# TempDataLogger.net
KiCad netlist of a schematic drawn in EasyEDA
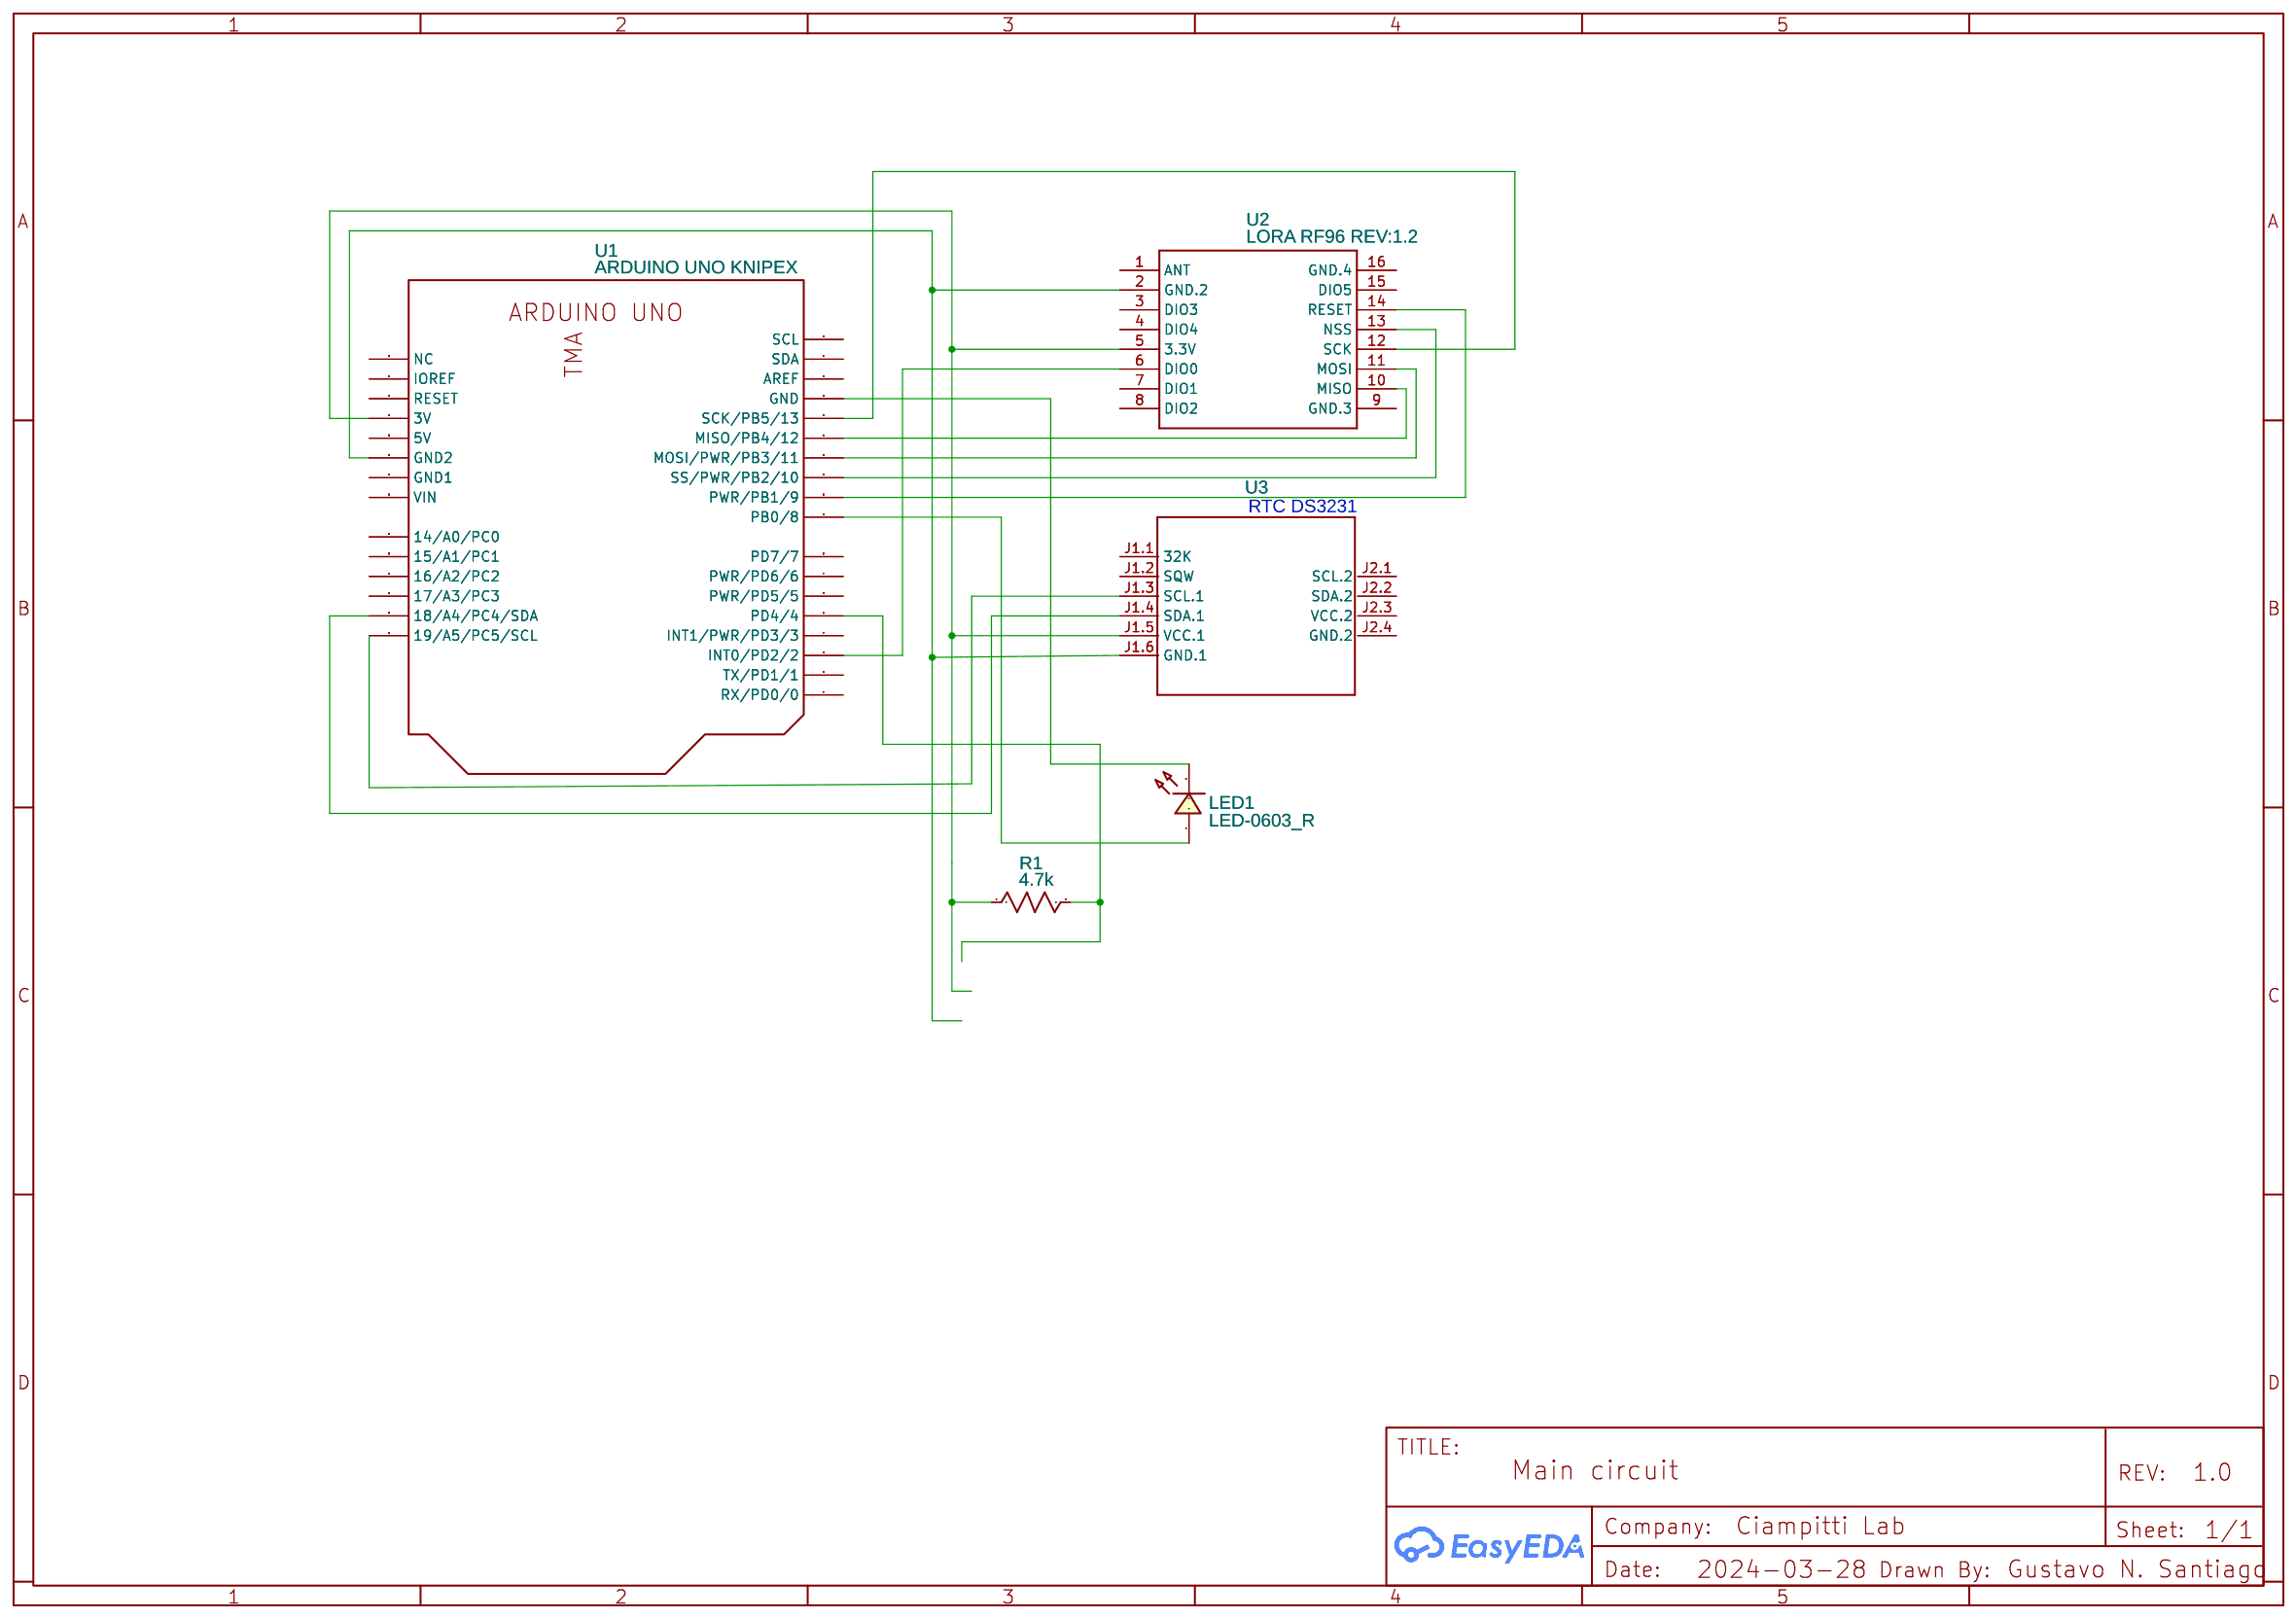
[diagram p0: Main circuit]
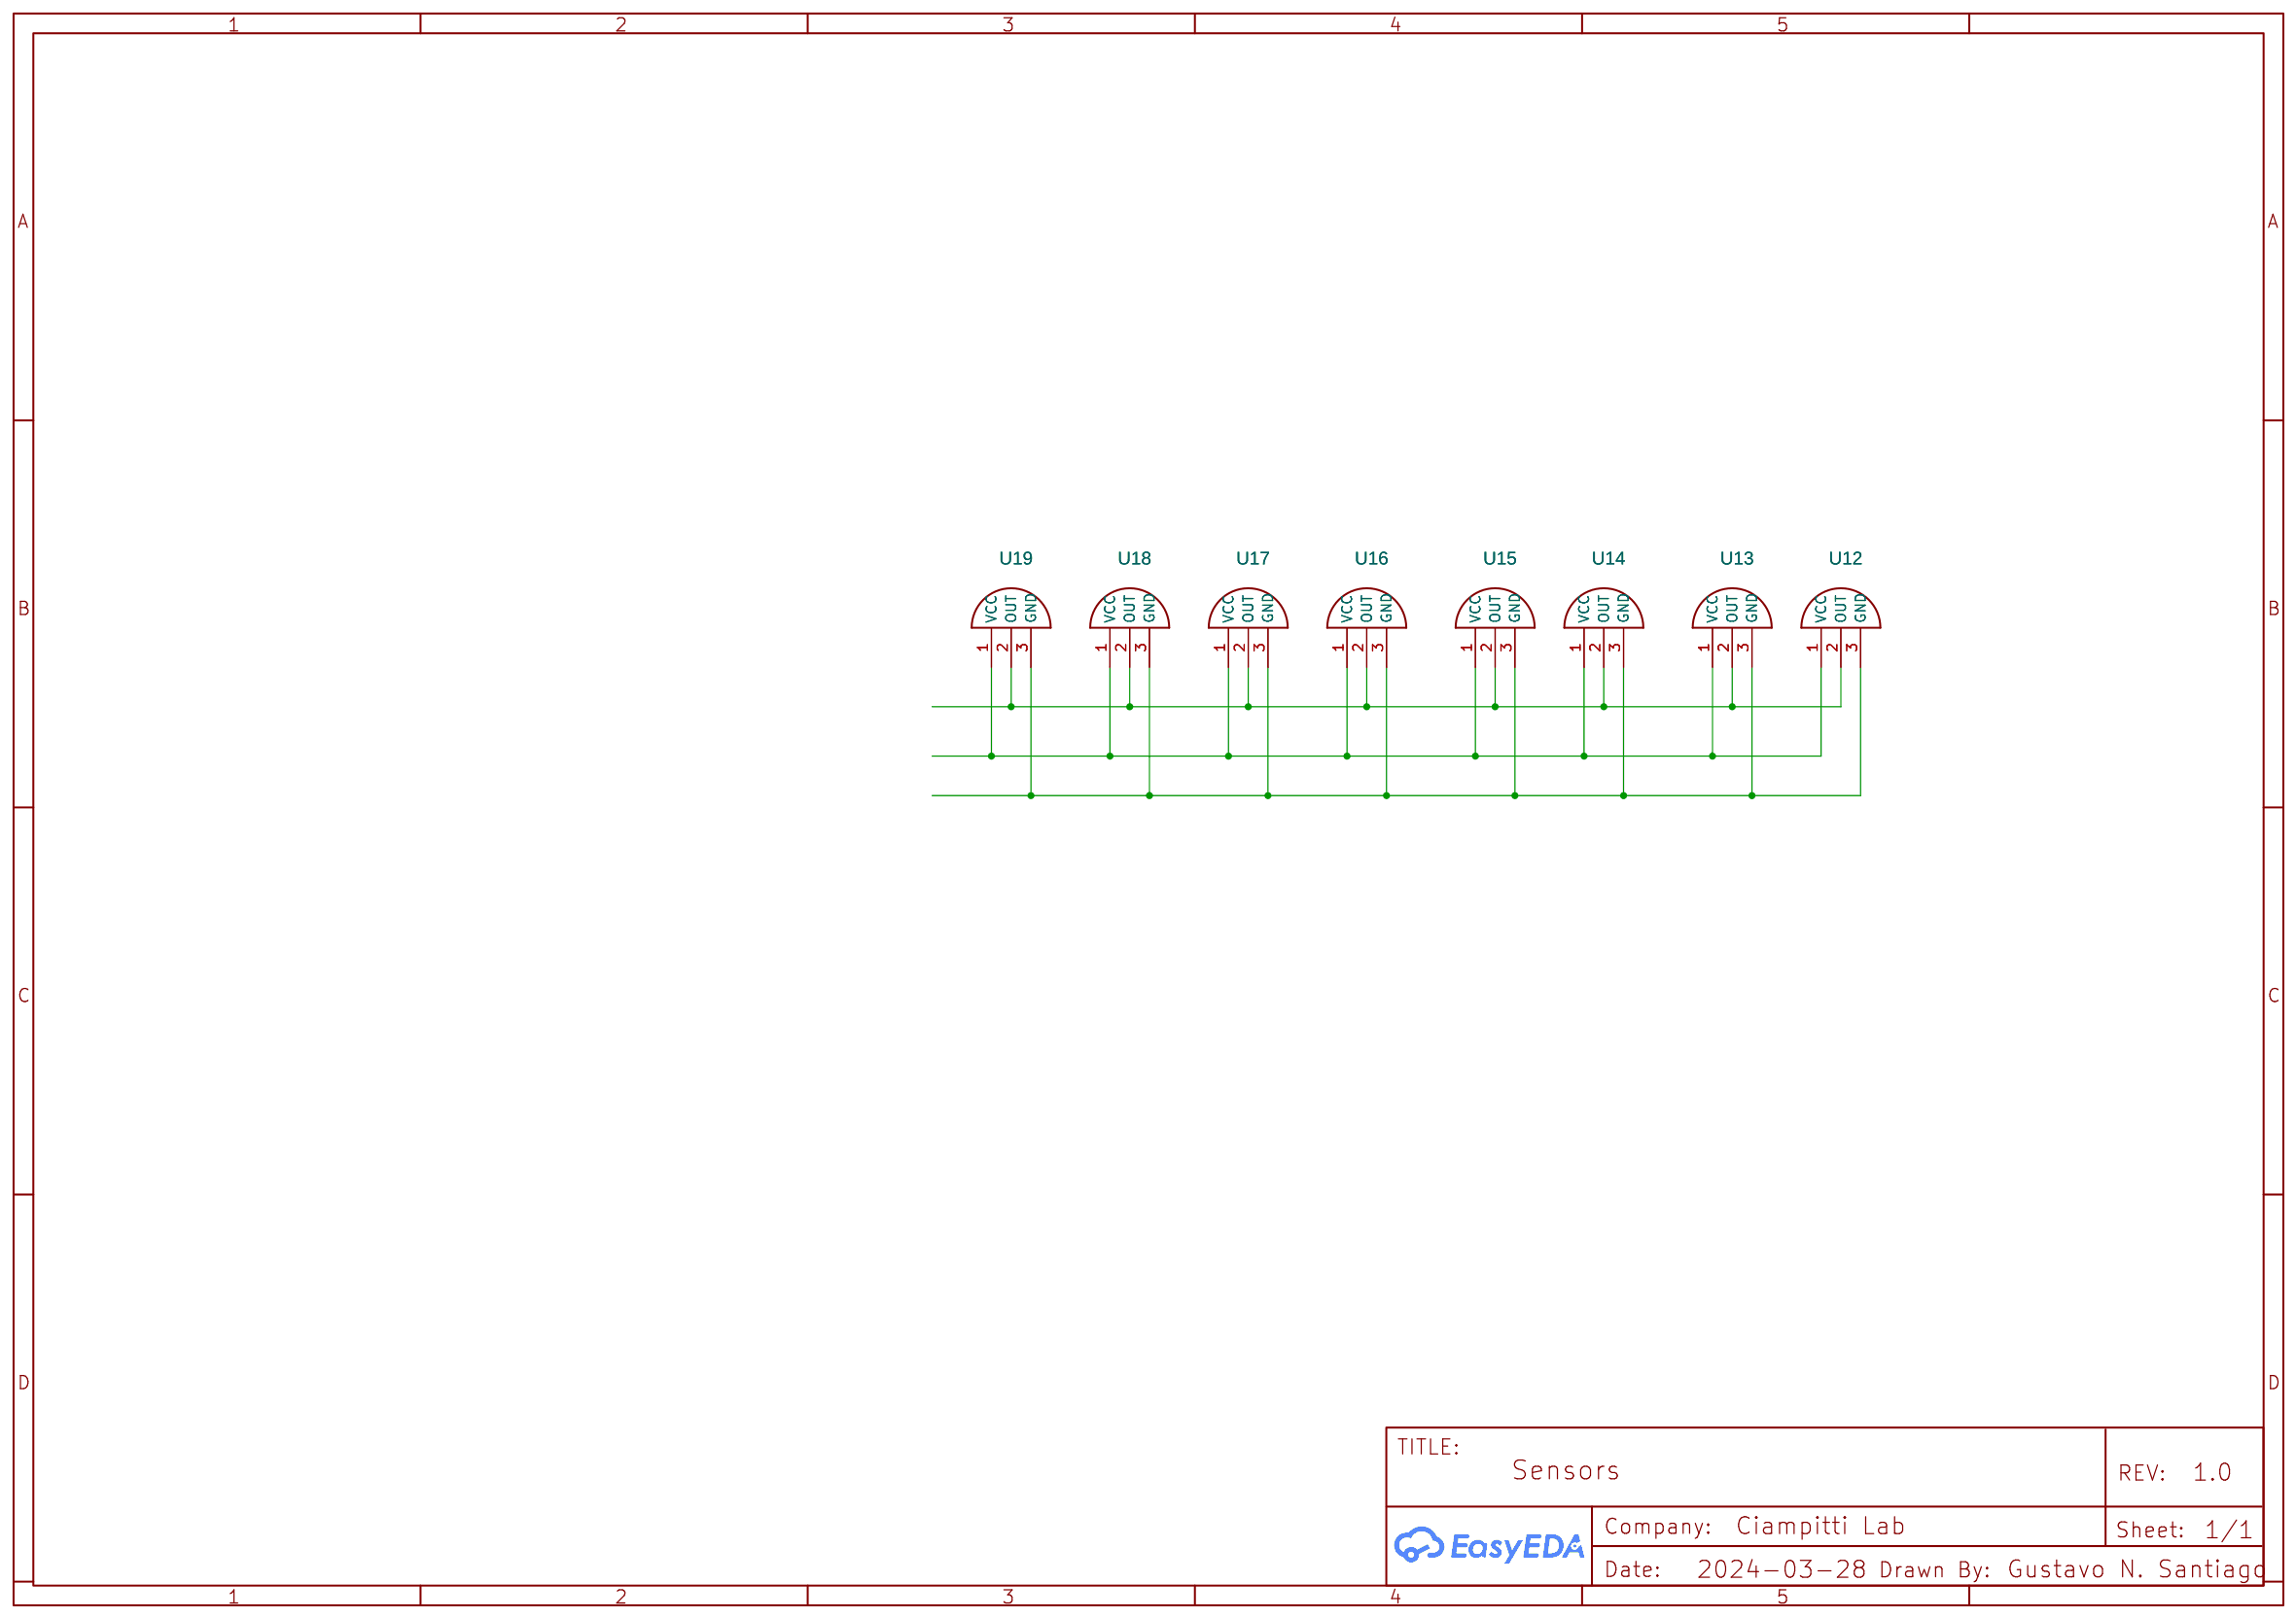
[diagram p1: Sensors]

(export (version "E")
  (design (tool "Eeschema 10.0.6"))
  (components
    (comp (ref "LED1")
      (value "LED-0603_R")
      (fields
        (field (name "Manufacturer Part") "19-217/R6C-AL1M2VY/3T")
        (field (name "Manufacturer") "EVERLIGHT(台湾亿光)")
      )
      (libsource (lib "") (part "LED-0603_R"))
    )
    (comp (ref "R1") (value "4.7k") (libsource (lib "") (part "R_0603_US")))
    (comp (ref "U1") (value "ARDUINO UNO KNIPEX") (libsource (lib "") (part "ARDUINO UNO KNIPEX")))
    (comp (ref "U2") (value "LORA RF96 REV:1.2") (libsource (lib "") (part "LORA RF96 REV{colon}1.2")))
    (comp (ref "U3") (value "NO") (libsource (lib "") (part "RTC-DS3231-AT24C32")))
    (comp (ref "U12")
      (value "NO")
      (fields (field (name "Manufacturer Part") "New SchematicLib"))
      (libsource (lib "") (part "DS18B20 TEMPERATURE"))
    )
    (comp (ref "U13")
      (value "NO")
      (fields (field (name "Manufacturer Part") "New SchematicLib"))
      (libsource (lib "") (part "DS18B20 TEMPERATURE"))
    )
    (comp (ref "U14")
      (value "NO")
      (fields (field (name "Manufacturer Part") "New SchematicLib"))
      (libsource (lib "") (part "DS18B20 TEMPERATURE"))
    )
    (comp (ref "U15")
      (value "NO")
      (fields (field (name "Manufacturer Part") "New SchematicLib"))
      (libsource (lib "") (part "DS18B20 TEMPERATURE"))
    )
    (comp (ref "U16")
      (value "NO")
      (fields (field (name "Manufacturer Part") "New SchematicLib"))
      (libsource (lib "") (part "DS18B20 TEMPERATURE"))
    )
    (comp (ref "U17")
      (value "NO")
      (fields (field (name "Manufacturer Part") "New SchematicLib"))
      (libsource (lib "") (part "DS18B20 TEMPERATURE"))
    )
    (comp (ref "U18")
      (value "NO")
      (fields (field (name "Manufacturer Part") "New SchematicLib"))
      (libsource (lib "") (part "DS18B20 TEMPERATURE"))
    )
    (comp (ref "U19")
      (value "NO")
      (fields (field (name "Manufacturer Part") "New SchematicLib"))
      (libsource (lib "") (part "DS18B20 TEMPERATURE"))
    )
  )
  (nets
    (net (code "1") (name "Net-(U1-3V)") (class "Default")
      (node (ref "R1") (pin "1") (pinfunction "1_1") (pintype "unspecified"))
      (node (ref "U1") (pin "29") (pinfunction "3V_29") (pintype "passive"))
      (node (ref "U2") (pin "5") (pinfunction "3.3V_5") (pintype "passive"))
      (node (ref "U3") (pin "J1.5") (pinfunction "VCC.1_J1.5") (pintype "bidirectional"))
    )
    (net (code "2") (name "Net-(U1-18{slash}A4{slash}PC4{slash}SDA)") (class "Default")
      (node (ref "U1") (pin "20") (pinfunction "18/A4/PC4/SDA_20") (pintype "unspecified"))
      (node (ref "U3") (pin "J1.4") (pinfunction "SDA.1_J1.4") (pintype "bidirectional"))
    )
    (net (code "3") (name "Net-(U1-19{slash}A5{slash}PC5{slash}SCL)") (class "Default")
      (node (ref "U1") (pin "19") (pinfunction "19/A5/PC5/SCL_19") (pintype "unspecified"))
      (node (ref "U3") (pin "J1.3") (pinfunction "SCL.1_J1.3") (pintype "bidirectional"))
    )
    (net (code "4") (name "Net-(U1-GND)") (class "Default")
      (node (ref "LED1") (pin "2") (pinfunction "2_2") (pintype "unspecified"))
      (node (ref "U1") (pin "15") (pinfunction "GND_15") (pintype "passive"))
    )
    (net (code "5") (name "Net-(U1-GND2)") (class "Default")
      (node (ref "U1") (pin "27") (pinfunction "GND2_27") (pintype "passive"))
      (node (ref "U2") (pin "2") (pinfunction "GND.2_2") (pintype "passive"))
      (node (ref "U3") (pin "J1.6") (pinfunction "GND.1_J1.6") (pintype "bidirectional"))
    )
    (net (code "6") (name "Net-(U1-INT0{slash}PD2{slash}2)") (class "Default")
      (node (ref "U1") (pin "3") (pinfunction "INT0/PD2/2_3") (pintype "unspecified"))
      (node (ref "U2") (pin "6") (pinfunction "DIO0_6") (pintype "unspecified"))
    )
    (net (code "7") (name "Net-(U1-MISO{slash}PB4{slash}12)") (class "Default")
      (node (ref "U1") (pin "13") (pinfunction "MISO/PB4/12_13") (pintype "unspecified"))
      (node (ref "U2") (pin "10") (pinfunction "MISO_10") (pintype "unspecified"))
    )
    (net (code "8") (name "Net-(U1-MOSI{slash}PWR{slash}PB3{slash}11)") (class "Default")
      (node (ref "U1") (pin "12") (pinfunction "MOSI/PWR/PB3/11_12") (pintype "unspecified"))
      (node (ref "U2") (pin "11") (pinfunction "MOSI_11") (pintype "unspecified"))
    )
    (net (code "9") (name "Net-(U1-PB0{slash}8)") (class "Default")
      (node (ref "LED1") (pin "1") (pinfunction "1_1") (pintype "unspecified"))
      (node (ref "U1") (pin "9") (pinfunction "PB0/8_9") (pintype "unspecified"))
    )
    (net (code "10") (name "Net-(U1-PD4{slash}4)") (class "Default")
      (node (ref "R1") (pin "2") (pinfunction "2_2") (pintype "unspecified"))
      (node (ref "U1") (pin "5") (pinfunction "PD4/4_5") (pintype "unspecified"))
    )
    (net (code "11") (name "Net-(U1-PWR{slash}PB1{slash}9)") (class "Default")
      (node (ref "U1") (pin "10") (pinfunction "PWR/PB1/9_10") (pintype "unspecified"))
      (node (ref "U2") (pin "14") (pinfunction "RESET_14") (pintype "unspecified"))
    )
    (net (code "12") (name "Net-(U1-SCK{slash}PB5{slash}13)") (class "Default")
      (node (ref "U1") (pin "14") (pinfunction "SCK/PB5/13_14") (pintype "unspecified"))
      (node (ref "U2") (pin "12") (pinfunction "SCK_12") (pintype "unspecified"))
    )
    (net (code "13") (name "Net-(U1-SS{slash}PWR{slash}PB2{slash}10)") (class "Default")
      (node (ref "U1") (pin "11") (pinfunction "SS/PWR/PB2/10_11") (pintype "unspecified"))
      (node (ref "U2") (pin "13") (pinfunction "NSS_13") (pintype "unspecified"))
    )
    (net (code "14") (name "Net-(U12-GND)") (class "Default")
      (node (ref "U12") (pin "3") (pinfunction "GND_3") (pintype "unspecified"))
      (node (ref "U13") (pin "3") (pinfunction "GND_3") (pintype "unspecified"))
      (node (ref "U14") (pin "3") (pinfunction "GND_3") (pintype "unspecified"))
      (node (ref "U15") (pin "3") (pinfunction "GND_3") (pintype "unspecified"))
      (node (ref "U16") (pin "3") (pinfunction "GND_3") (pintype "unspecified"))
      (node (ref "U17") (pin "3") (pinfunction "GND_3") (pintype "unspecified"))
      (node (ref "U18") (pin "3") (pinfunction "GND_3") (pintype "unspecified"))
      (node (ref "U19") (pin "3") (pinfunction "GND_3") (pintype "unspecified"))
    )
    (net (code "15") (name "Net-(U12-OUT)") (class "Default")
      (node (ref "U12") (pin "2") (pinfunction "OUT_2") (pintype "unspecified"))
      (node (ref "U13") (pin "2") (pinfunction "OUT_2") (pintype "unspecified"))
      (node (ref "U14") (pin "2") (pinfunction "OUT_2") (pintype "unspecified"))
      (node (ref "U15") (pin "2") (pinfunction "OUT_2") (pintype "unspecified"))
      (node (ref "U16") (pin "2") (pinfunction "OUT_2") (pintype "unspecified"))
      (node (ref "U17") (pin "2") (pinfunction "OUT_2") (pintype "unspecified"))
      (node (ref "U18") (pin "2") (pinfunction "OUT_2") (pintype "unspecified"))
      (node (ref "U19") (pin "2") (pinfunction "OUT_2") (pintype "unspecified"))
    )
    (net (code "16") (name "Net-(U12-VCC)") (class "Default")
      (node (ref "U12") (pin "1") (pinfunction "VCC_1") (pintype "unspecified"))
      (node (ref "U13") (pin "1") (pinfunction "VCC_1") (pintype "unspecified"))
      (node (ref "U14") (pin "1") (pinfunction "VCC_1") (pintype "unspecified"))
      (node (ref "U15") (pin "1") (pinfunction "VCC_1") (pintype "unspecified"))
      (node (ref "U16") (pin "1") (pinfunction "VCC_1") (pintype "unspecified"))
      (node (ref "U17") (pin "1") (pinfunction "VCC_1") (pintype "unspecified"))
      (node (ref "U18") (pin "1") (pinfunction "VCC_1") (pintype "unspecified"))
      (node (ref "U19") (pin "1") (pinfunction "VCC_1") (pintype "unspecified"))
    )
    (net (code "17") (name "unconnected-(U1-5V-Pad28)") (class "Default")
      (node (ref "U1") (pin "28") (pinfunction "5V_28") (pintype "passive"))
    )
    (net (code "18") (name "unconnected-(U1-14{slash}A0{slash}PC0-Pad24)") (class "Default")
      (node (ref "U1") (pin "24") (pinfunction "14/A0/PC0_24") (pintype "unspecified"))
    )
    (net (code "19") (name "unconnected-(U1-15{slash}A1{slash}PC1-Pad23)") (class "Default")
      (node (ref "U1") (pin "23") (pinfunction "15/A1/PC1_23") (pintype "unspecified"))
    )
    (net (code "20") (name "unconnected-(U1-16{slash}A2{slash}PC2-Pad22)") (class "Default")
      (node (ref "U1") (pin "22") (pinfunction "16/A2/PC2_22") (pintype "unspecified"))
    )
    (net (code "21") (name "unconnected-(U1-17{slash}A3{slash}PC3-Pad21)") (class "Default")
      (node (ref "U1") (pin "21") (pinfunction "17/A3/PC3_21") (pintype "unspecified"))
    )
    (net (code "22") (name "unconnected-(U1-AREF-Pad16)") (class "Default")
      (node (ref "U1") (pin "16") (pinfunction "AREF_16") (pintype "unspecified"))
    )
    (net (code "23") (name "unconnected-(U1-GND1-Pad26)") (class "Default")
      (node (ref "U1") (pin "26") (pinfunction "GND1_26") (pintype "passive"))
    )
    (net (code "24") (name "unconnected-(U1-INT1{slash}PWR{slash}PD3{slash}3-Pad4)") (class "Default")
      (node (ref "U1") (pin "4") (pinfunction "INT1/PWR/PD3/3_4") (pintype "unspecified"))
    )
    (net (code "25") (name "unconnected-(U1-IOREF-Pad31)") (class "Default")
      (node (ref "U1") (pin "31") (pinfunction "IOREF_31") (pintype "unspecified"))
    )
    (net (code "26") (name "unconnected-(U1-NC-Pad32)") (class "Default")
      (node (ref "U1") (pin "32") (pinfunction "NC_32") (pintype "unspecified"))
    )
    (net (code "27") (name "unconnected-(U1-PD7{slash}7-Pad8)") (class "Default")
      (node (ref "U1") (pin "8") (pinfunction "PD7/7_8") (pintype "unspecified"))
    )
    (net (code "28") (name "unconnected-(U1-PWR{slash}PD5{slash}5-Pad6)") (class "Default")
      (node (ref "U1") (pin "6") (pinfunction "PWR/PD5/5_6") (pintype "unspecified"))
    )
    (net (code "29") (name "unconnected-(U1-PWR{slash}PD6{slash}6-Pad7)") (class "Default")
      (node (ref "U1") (pin "7") (pinfunction "PWR/PD6/6_7") (pintype "unspecified"))
    )
    (net (code "30") (name "unconnected-(U1-RESET-Pad30)") (class "Default")
      (node (ref "U1") (pin "30") (pinfunction "RESET_30") (pintype "unspecified"))
    )
    (net (code "31") (name "unconnected-(U1-RX{slash}PD0{slash}0-Pad1)") (class "Default")
      (node (ref "U1") (pin "1") (pinfunction "RX/PD0/0_1") (pintype "unspecified"))
    )
    (net (code "32") (name "unconnected-(U1-SCL-Pad18)") (class "Default")
      (node (ref "U1") (pin "18") (pinfunction "SCL_18") (pintype "unspecified"))
    )
    (net (code "33") (name "unconnected-(U1-SDA-Pad17)") (class "Default")
      (node (ref "U1") (pin "17") (pinfunction "SDA_17") (pintype "unspecified"))
    )
    (net (code "34") (name "unconnected-(U1-TX{slash}PD1{slash}1-Pad2)") (class "Default")
      (node (ref "U1") (pin "2") (pinfunction "TX/PD1/1_2") (pintype "unspecified"))
    )
    (net (code "35") (name "unconnected-(U1-VIN-Pad25)") (class "Default")
      (node (ref "U1") (pin "25") (pinfunction "VIN_25") (pintype "passive"))
    )
    (net (code "36") (name "unconnected-(U2-ANT-Pad1)") (class "Default")
      (node (ref "U2") (pin "1") (pinfunction "ANT_1") (pintype "passive"))
    )
    (net (code "37") (name "unconnected-(U2-DIO1-Pad7)") (class "Default")
      (node (ref "U2") (pin "7") (pinfunction "DIO1_7") (pintype "unspecified"))
    )
    (net (code "38") (name "unconnected-(U2-DIO2-Pad8)") (class "Default")
      (node (ref "U2") (pin "8") (pinfunction "DIO2_8") (pintype "unspecified"))
    )
    (net (code "39") (name "unconnected-(U2-DIO3-Pad3)") (class "Default")
      (node (ref "U2") (pin "3") (pinfunction "DIO3_3") (pintype "unspecified"))
    )
    (net (code "40") (name "unconnected-(U2-DIO4-Pad4)") (class "Default")
      (node (ref "U2") (pin "4") (pinfunction "DIO4_4") (pintype "unspecified"))
    )
    (net (code "41") (name "unconnected-(U2-DIO5-Pad15)") (class "Default")
      (node (ref "U2") (pin "15") (pinfunction "DIO5_15") (pintype "unspecified"))
    )
    (net (code "42") (name "unconnected-(U2-GND.3-Pad9)") (class "Default")
      (node (ref "U2") (pin "9") (pinfunction "GND.3_9") (pintype "passive"))
    )
    (net (code "43") (name "unconnected-(U2-GND.4-Pad16)") (class "Default")
      (node (ref "U2") (pin "16") (pinfunction "GND.4_16") (pintype "passive"))
    )
    (net (code "44") (name "unconnected-(U3-32K-PadJ1.1)") (class "Default")
      (node (ref "U3") (pin "J1.1") (pinfunction "32K_J1.1") (pintype "bidirectional"))
    )
    (net (code "45") (name "unconnected-(U3-GND.2-PadJ2.4)") (class "Default")
      (node (ref "U3") (pin "J2.4") (pinfunction "GND.2_J2.4") (pintype "bidirectional"))
    )
    (net (code "46") (name "unconnected-(U3-SCL.2-PadJ2.1)") (class "Default")
      (node (ref "U3") (pin "J2.1") (pinfunction "SCL.2_J2.1") (pintype "bidirectional"))
    )
    (net (code "47") (name "unconnected-(U3-SDA.2-PadJ2.2)") (class "Default")
      (node (ref "U3") (pin "J2.2") (pinfunction "SDA.2_J2.2") (pintype "bidirectional"))
    )
    (net (code "48") (name "unconnected-(U3-SQW-PadJ1.2)") (class "Default")
      (node (ref "U3") (pin "J1.2") (pinfunction "SQW_J1.2") (pintype "bidirectional"))
    )
    (net (code "49") (name "unconnected-(U3-VCC.2-PadJ2.3)") (class "Default")
      (node (ref "U3") (pin "J2.3") (pinfunction "VCC.2_J2.3") (pintype "bidirectional"))
    )
  )
)
